# SL_Config_2E.net
KiCad netlist of a schematic drawn in Altium Designer
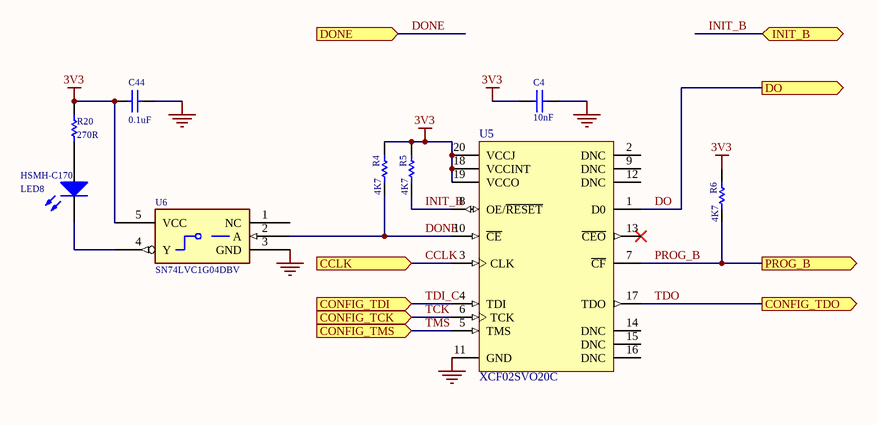
[diagram p0: SL_Config_2E.SchDoc]

(export (version "E")
  (design (tool "Eeschema 10.0.6"))
  (components
    (comp (ref "C4")
      (value "10nF")
      (footprint "CC1608-0603")
      (description "Capacitor")
      (libsource (lib "Test1") (part "CAP"))
    )
    (comp (ref "C44")
      (value "0.1uF")
      (footprint "Altium Nanoboard Project:CC2012-0805")
      (description "Capacitor")
      (libsource (lib "Altium Nanoboard Project") (part "CAP"))
    )
    (comp (ref "LED8")
      (value "HSMH-C170")
      (footprint "Altium Nanoboard Project:SMD _LED")
      (description "Typical RED GaAs SMD LED Agilent make")
      (libsource (lib "Altium Nanoboard Project") (part "HSMX-C670"))
    )
    (comp (ref "R4")
      (value "4K7")
      (footprint "CR2012-0805")
      (description "Resistor")
      (libsource (lib "PassiveSMD") (part "RES"))
    )
    (comp (ref "R5")
      (value "4K7")
      (footprint "CR2012-0805")
      (description "Resistor")
      (libsource (lib "PassiveSMD") (part "RES"))
    )
    (comp (ref "R6")
      (value "4K7")
      (footprint "CR2012-0805")
      (description "Resistor")
      (libsource (lib "PassiveSMD") (part "RES"))
    )
    (comp (ref "R20")
      (value "270R")
      (footprint "CR2012-0805")
      (description "Resistor")
      (libsource (lib "PassiveSMD") (part "RES"))
    )
    (comp (ref "U5")
      (value "XCF02SVO20C")
      (footprint "VO20")
      (libsource (lib "Xilinx XCF") (part "XCF02SVO20C"))
    )
    (comp (ref "U6")
      (value "SN74LVC1G04DBV")
      (footprint "Altium Nanoboard Project:SO-G5/P.95")
      (fields (field (name "MANUFACTURER") "TI"))
      (libsource (lib "Altium Nanoboard Project") (part "SN74AHC1G04DBVR"))
    )
  )
  (nets
    (net (code "1") (name "/CCLK") (class "Default")
      (node (ref "U5") (pin "3") (pinfunction "CLK_3") (pintype "input"))
    )
    (net (code "2") (name "/DO") (class "Default")
      (node (ref "U5") (pin "1") (pinfunction "D0_1") (pintype "tri_state"))
    )
    (net (code "3") (name "/DONE") (class "Default")
      (node (ref "R4") (pin "2") (pinfunction "2_2") (pintype "passive"))
      (node (ref "U5") (pin "10") (pinfunction "~{CE}_10") (pintype "input"))
      (node (ref "U6") (pin "2") (pinfunction "A_2") (pintype "input"))
    )
    (net (code "4") (name "/INIT_B") (class "Default")
      (node (ref "R5") (pin "2") (pinfunction "2_2") (pintype "passive"))
      (node (ref "U5") (pin "8") (pinfunction "OE/~{RESET}_8") (pintype "bidirectional"))
    )
    (net (code "5") (name "/PROG_B") (class "Default")
      (node (ref "R6") (pin "2") (pinfunction "2_2") (pintype "passive"))
      (node (ref "U5") (pin "7") (pinfunction "~{CF}_7") (pintype "open_collector"))
    )
    (net (code "6") (name "/TCK") (class "Default")
      (node (ref "U5") (pin "6") (pinfunction "TCK_6") (pintype "input"))
    )
    (net (code "7") (name "/TDI_C") (class "Default")
      (node (ref "U5") (pin "4") (pinfunction "TDI_4") (pintype "input"))
    )
    (net (code "8") (name "/TDO") (class "Default")
      (node (ref "U5") (pin "17") (pinfunction "TDO_17") (pintype "output"))
    )
    (net (code "9") (name "/TMS") (class "Default")
      (node (ref "U5") (pin "5") (pinfunction "TMS_5") (pintype "input"))
    )
    (net (code "10") (name "3V3") (class "Default")
      (node (ref "C4") (pin "1") (pinfunction "1_1") (pintype "passive"))
      (node (ref "C44") (pin "2") (pinfunction "2_2") (pintype "passive"))
      (node (ref "R20") (pin "2") (pinfunction "2_2") (pintype "passive"))
      (node (ref "R4") (pin "1") (pinfunction "1_1") (pintype "passive"))
      (node (ref "R5") (pin "1") (pinfunction "1_1") (pintype "passive"))
      (node (ref "R6") (pin "1") (pinfunction "1_1") (pintype "passive"))
      (node (ref "U5") (pin "18") (pinfunction "VCCINT_18") (pintype "power_in"))
      (node (ref "U5") (pin "19") (pinfunction "VCCO_19") (pintype "power_in"))
      (node (ref "U5") (pin "20") (pinfunction "VCCJ_20") (pintype "power_in"))
      (node (ref "U6") (pin "5") (pinfunction "VCC_5") (pintype "power_in"))
    )
    (net (code "11") (name "GND") (class "Default")
      (node (ref "C4") (pin "2") (pinfunction "2_2") (pintype "passive"))
      (node (ref "C44") (pin "1") (pinfunction "1_1") (pintype "passive"))
      (node (ref "U5") (pin "11") (pinfunction "GND_11") (pintype "power_in"))
      (node (ref "U6") (pin "3") (pinfunction "GND_3") (pintype "power_in"))
    )
    (net (code "12") (name "Net-(LED8-A)") (class "Default")
      (node (ref "LED8") (pin "1") (pinfunction "A_1") (pintype "passive"))
      (node (ref "R20") (pin "1") (pinfunction "1_1") (pintype "passive"))
    )
    (net (code "13") (name "Net-(LED8-K)") (class "Default")
      (node (ref "LED8") (pin "2") (pinfunction "K_2") (pintype "passive"))
      (node (ref "U6") (pin "4") (pinfunction "Y_4") (pintype "output"))
    )
    (net (code "14") (name "unconnected-(U5-DNC-Pad2)") (class "Default")
      (node (ref "U5") (pin "2") (pinfunction "DNC_2") (pintype "passive"))
    )
    (net (code "15") (name "unconnected-(U5-DNC-Pad9)") (class "Default")
      (node (ref "U5") (pin "9") (pinfunction "DNC_9") (pintype "passive"))
    )
    (net (code "16") (name "unconnected-(U5-DNC-Pad12)") (class "Default")
      (node (ref "U5") (pin "12") (pinfunction "DNC_12") (pintype "passive"))
    )
    (net (code "17") (name "unconnected-(U5-DNC-Pad14)") (class "Default")
      (node (ref "U5") (pin "14") (pinfunction "DNC_14") (pintype "passive"))
    )
    (net (code "18") (name "unconnected-(U5-DNC-Pad15)") (class "Default")
      (node (ref "U5") (pin "15") (pinfunction "DNC_15") (pintype "passive"))
    )
    (net (code "19") (name "unconnected-(U5-DNC-Pad16)") (class "Default")
      (node (ref "U5") (pin "16") (pinfunction "DNC_16") (pintype "passive"))
    )
    (net (code "20") (name "unconnected-(U5-~{CEO}-Pad13)") (class "Default")
      (node (ref "U5") (pin "13") (pinfunction "~{CEO}_13") (pintype "output+no_connect"))
    )
    (net (code "21") (name "unconnected-(U6-NC-Pad1)") (class "Default")
      (node (ref "U6") (pin "1") (pinfunction "NC_1") (pintype "passive"))
    )
  )
)
